# connectors.net
KiCad netlist of a schematic drawn in Altium Designer
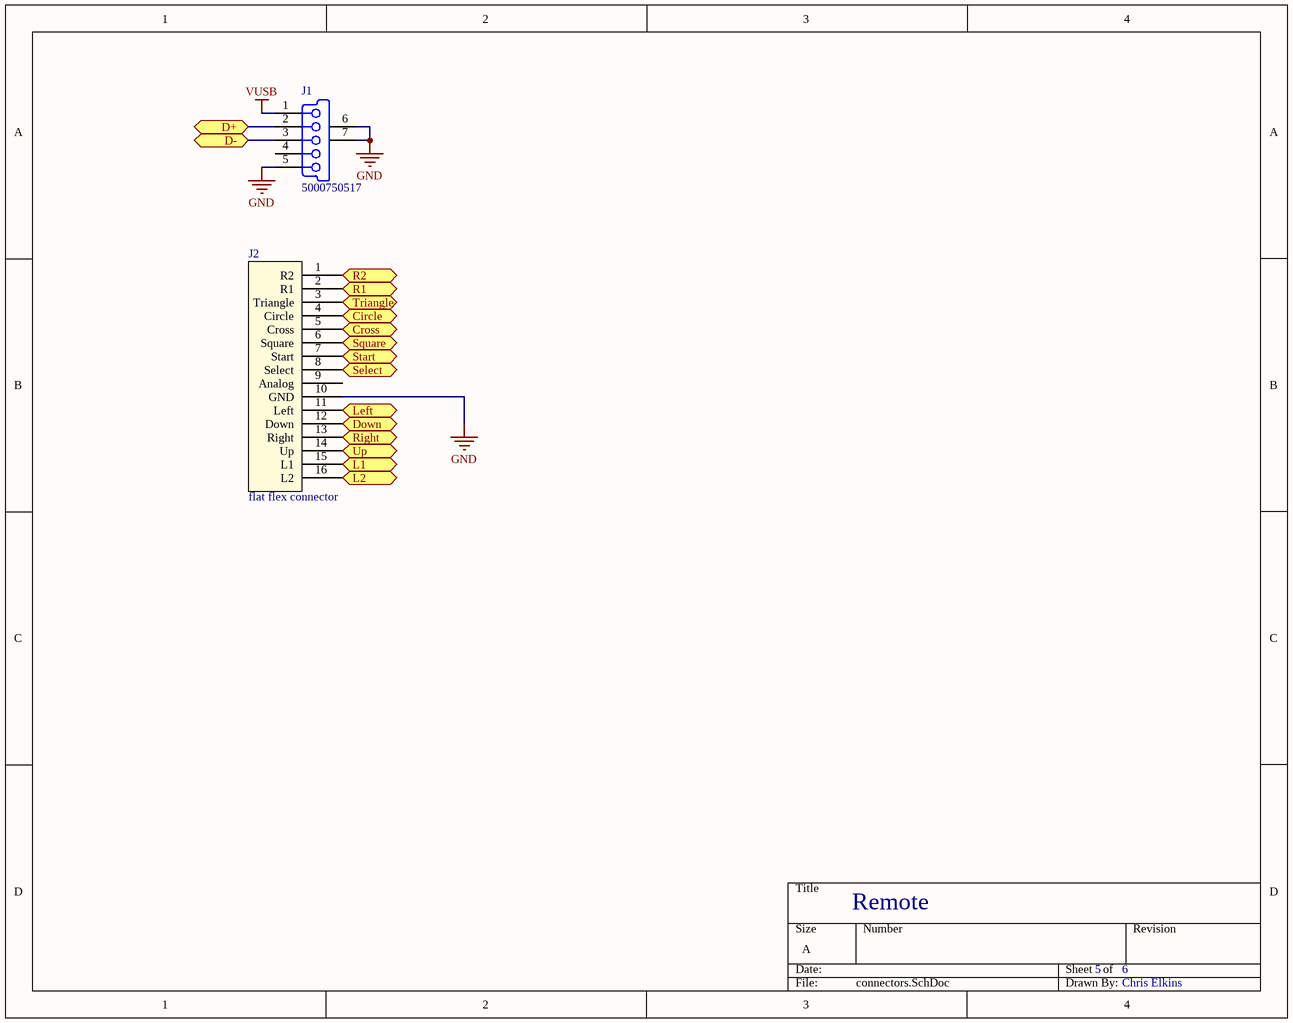
[diagram p0: connectors.SchDoc]

(export (version "E")
  (design (tool "Eeschema 10.0.6"))
  (components
    (comp (ref "J1")
      (value "5000750517")
      (footprint "5000750517")
      (fields (field (name "PUBLISHER") "Altium Limited"))
      (libsource (lib "Molex Serial Bus Mini USB") (part "5000750517"))
    )
    (comp (ref "J2")
      (value "flat flex connector")
      (footprint "flex con")
      (libsource (lib "Integrated_Library1") (part "flat flex connector"))
    )
  )
  (nets
    (net (code "1") (name "/Circle") (class "Default")
      (node (ref "J2") (pin "4") (pinfunction "Circle_4") (pintype "passive"))
    )
    (net (code "2") (name "/Cross") (class "Default")
      (node (ref "J2") (pin "5") (pinfunction "Cross_5") (pintype "passive"))
    )
    (net (code "3") (name "/D+") (class "Default")
      (node (ref "J1") (pin "2") (pinfunction "D-_2") (pintype "passive"))
    )
    (net (code "4") (name "/D-") (class "Default")
      (node (ref "J1") (pin "3") (pinfunction "D+_3") (pintype "passive"))
    )
    (net (code "5") (name "/Down") (class "Default")
      (node (ref "J2") (pin "12") (pinfunction "Down_12") (pintype "passive"))
    )
    (net (code "6") (name "/L1") (class "Default")
      (node (ref "J2") (pin "15") (pinfunction "L1_15") (pintype "passive"))
    )
    (net (code "7") (name "/L2") (class "Default")
      (node (ref "J2") (pin "16") (pinfunction "L2_16") (pintype "passive"))
    )
    (net (code "8") (name "/Left") (class "Default")
      (node (ref "J2") (pin "11") (pinfunction "Left_11") (pintype "passive"))
    )
    (net (code "9") (name "/R1") (class "Default")
      (node (ref "J2") (pin "2") (pinfunction "R1_2") (pintype "passive"))
    )
    (net (code "10") (name "/R2") (class "Default")
      (node (ref "J2") (pin "1") (pinfunction "R2_1") (pintype "passive"))
    )
    (net (code "11") (name "/Right") (class "Default")
      (node (ref "J2") (pin "13") (pinfunction "Right_13") (pintype "passive"))
    )
    (net (code "12") (name "/Select") (class "Default")
      (node (ref "J2") (pin "8") (pinfunction "Select_8") (pintype "passive"))
    )
    (net (code "13") (name "/Square") (class "Default")
      (node (ref "J2") (pin "6") (pinfunction "Square_6") (pintype "passive"))
    )
    (net (code "14") (name "/Start") (class "Default")
      (node (ref "J2") (pin "7") (pinfunction "Start_7") (pintype "passive"))
    )
    (net (code "15") (name "/Triangle") (class "Default")
      (node (ref "J2") (pin "3") (pinfunction "Triangle_3") (pintype "passive"))
    )
    (net (code "16") (name "/Up") (class "Default")
      (node (ref "J2") (pin "14") (pinfunction "Up_14") (pintype "passive"))
    )
    (net (code "17") (name "GND") (class "Default")
      (node (ref "J1") (pin "5") (pinfunction "GND_5") (pintype "passive"))
      (node (ref "J1") (pin "6") (pinfunction "MH1_6") (pintype "passive"))
      (node (ref "J1") (pin "7") (pinfunction "MH2_7") (pintype "passive"))
      (node (ref "J2") (pin "10") (pinfunction "GND_10") (pintype "passive"))
    )
    (net (code "18") (name "VUSB") (class "Default")
      (node (ref "J1") (pin "1") (pinfunction "V_BUS_1") (pintype "passive"))
    )
    (net (code "19") (name "unconnected-(J1-ID-Pad4)") (class "Default")
      (node (ref "J1") (pin "4") (pinfunction "ID_4") (pintype "passive"))
    )
    (net (code "20") (name "unconnected-(J2-Analog-Pad9)") (class "Default")
      (node (ref "J2") (pin "9") (pinfunction "Analog_9") (pintype "passive"))
    )
  )
)
